# backplane.net
KiCad netlist of a schematic drawn in EAGLE
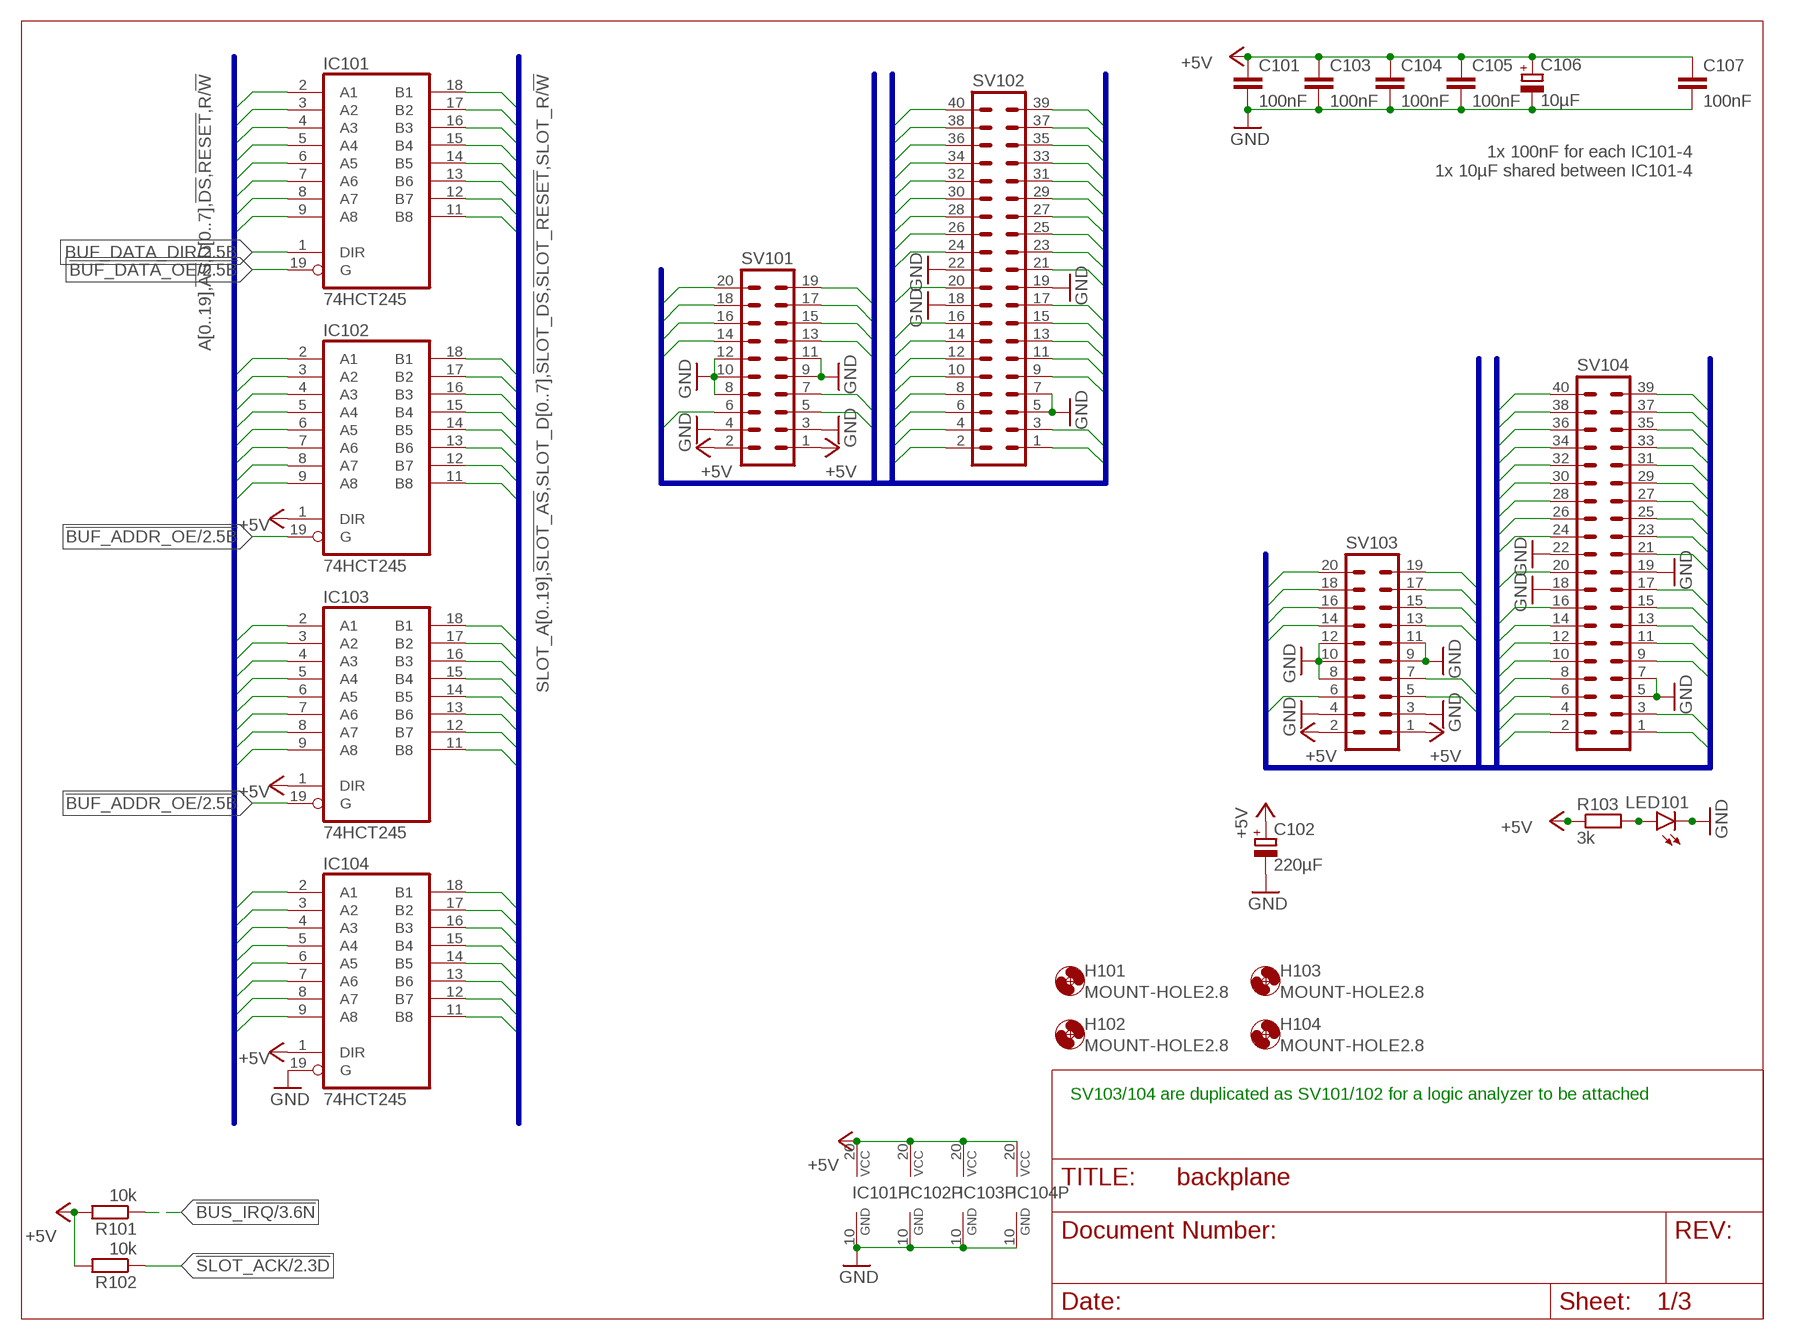
[diagram p0: schematic, sheet 1]
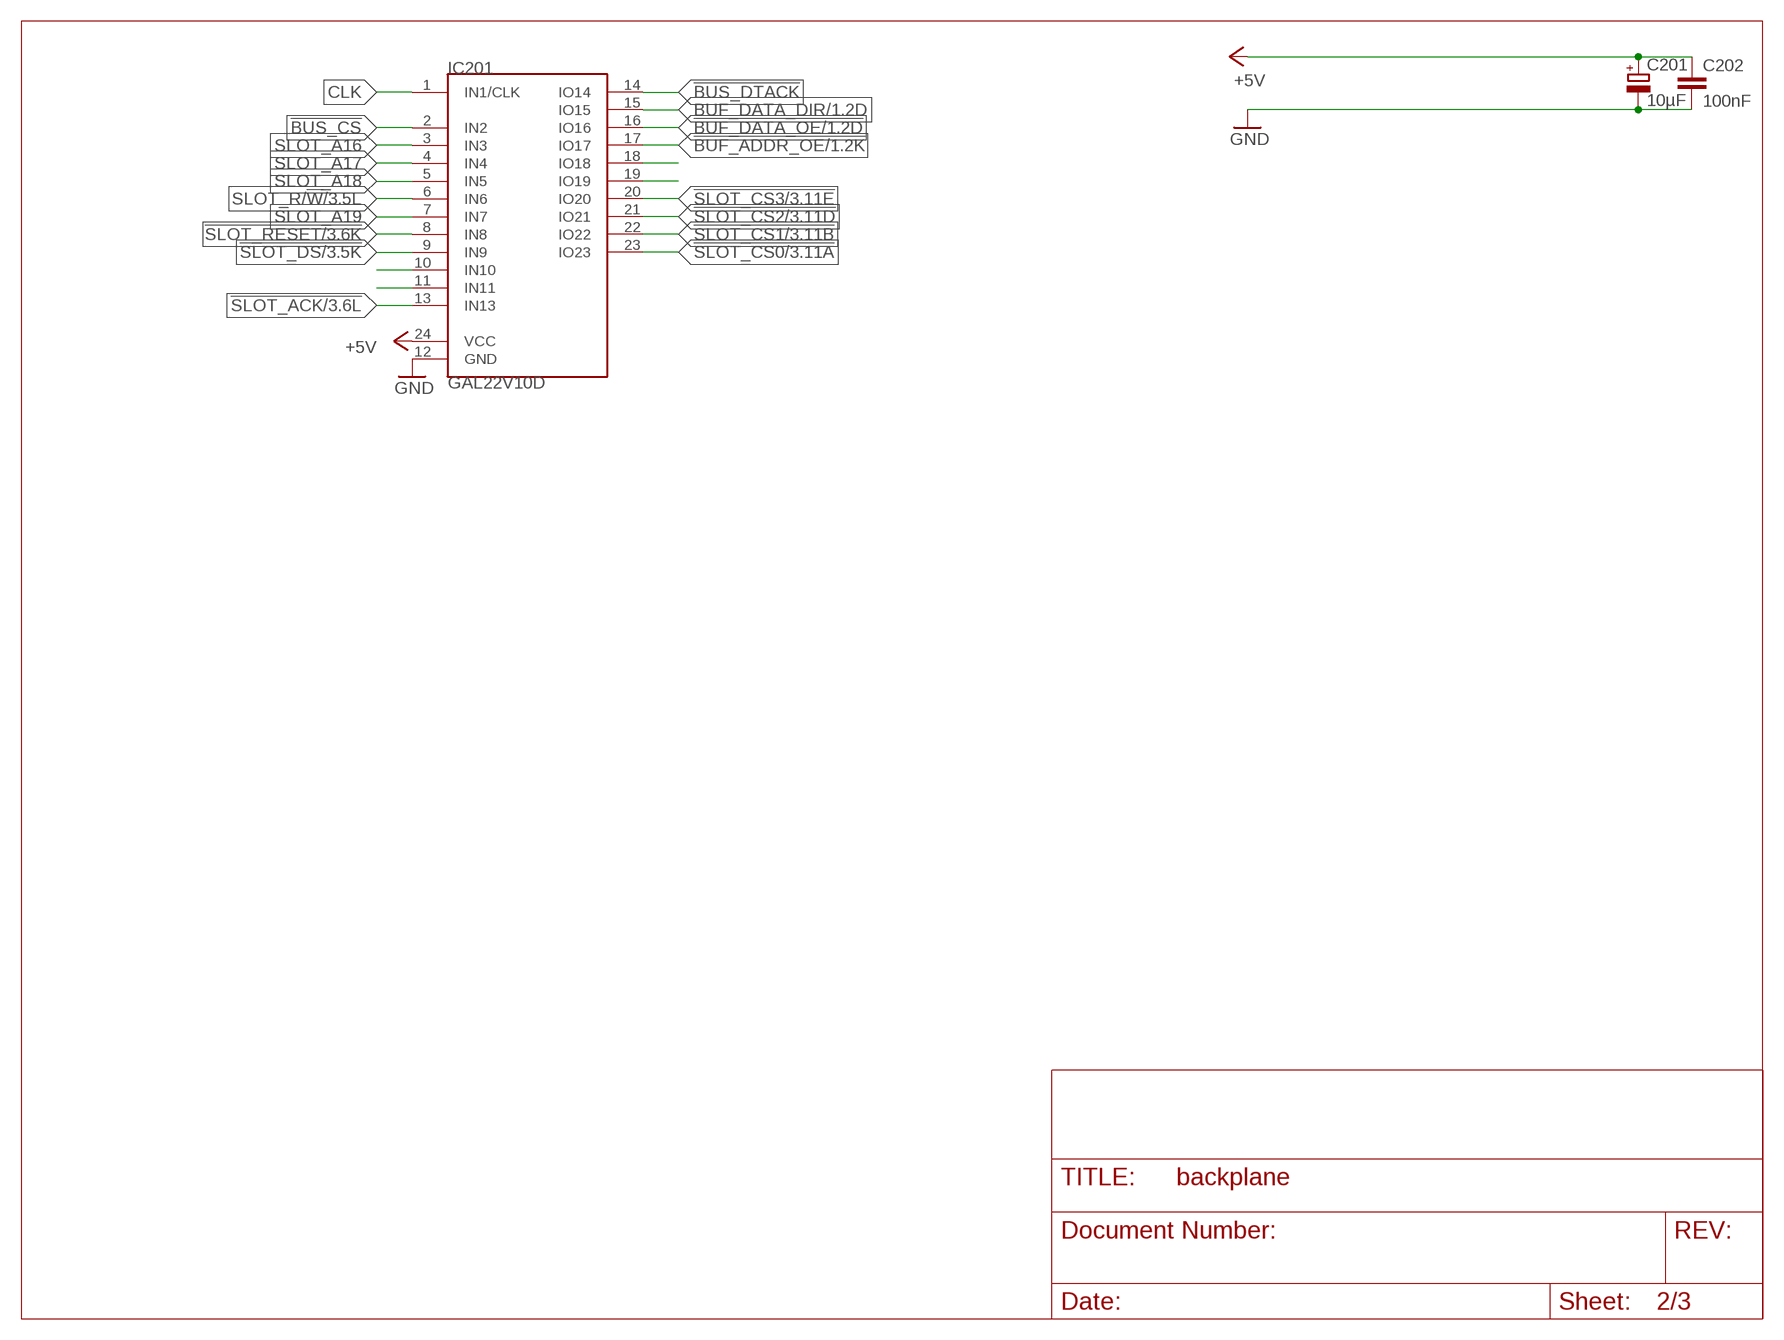
[diagram p1: schematic, sheet 2]
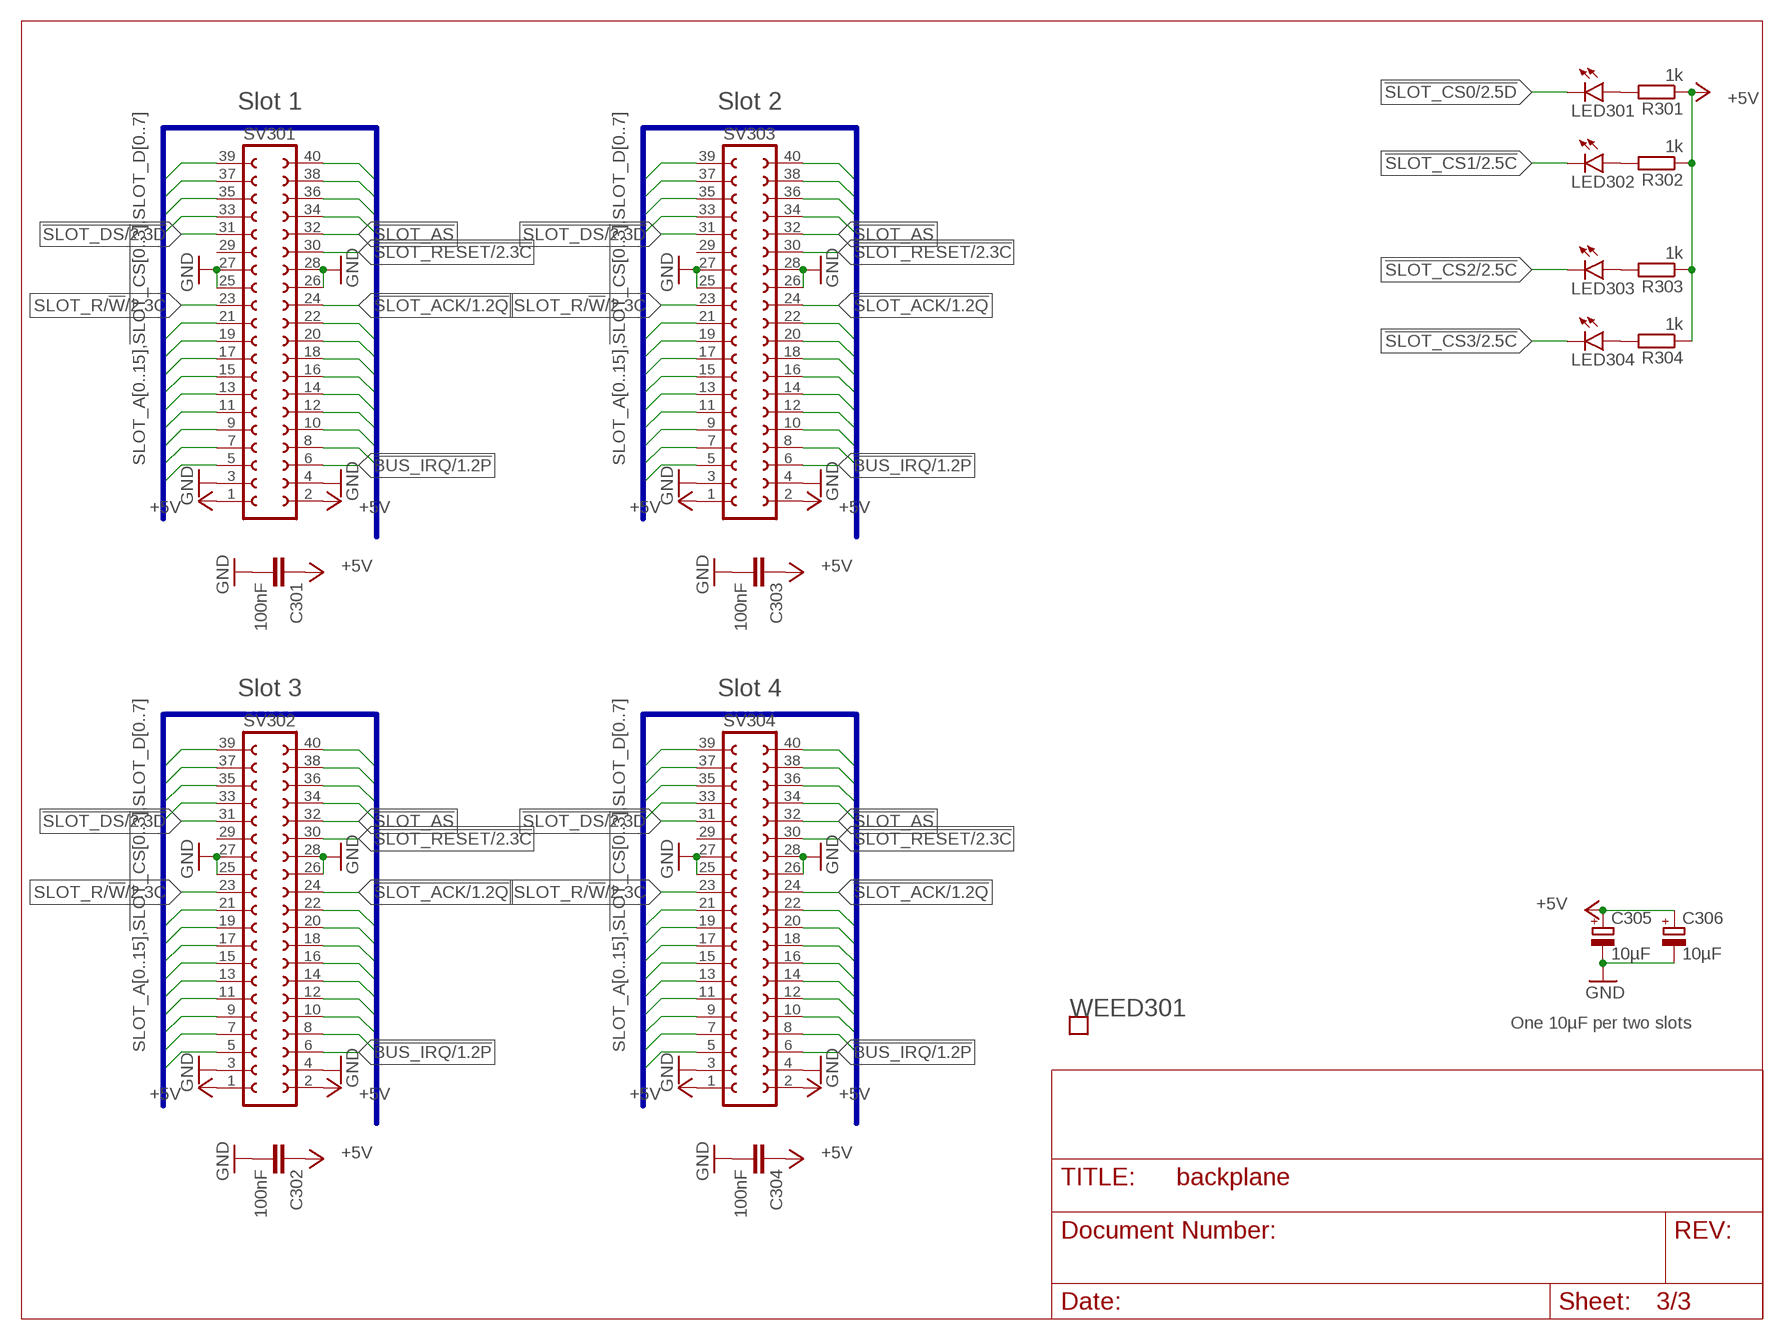
[diagram p2: schematic, sheet 3]

(export (version "E")
  (design (tool "Eeschema 10.0.6"))
  (components
    (comp (ref "C301")
      (value "100nF")
      (footprint "eagle-import:C0805")
      (libsource (lib "eagle-import") (part "C-EUC0805"))
    )
    (comp (ref "C302")
      (value "100nF")
      (footprint "eagle-import:C0805")
      (libsource (lib "eagle-import") (part "C-EUC0805"))
    )
    (comp (ref "C303")
      (value "100nF")
      (footprint "eagle-import:C0805")
      (libsource (lib "eagle-import") (part "C-EUC0805"))
    )
    (comp (ref "C304")
      (value "100nF")
      (footprint "eagle-import:C0805")
      (libsource (lib "eagle-import") (part "C-EUC0805"))
    )
    (comp (ref "C305")
      (value "10µF")
      (footprint "eagle-import:SMC_B")
      (libsource (lib "eagle-import") (part "CPOL-EUSMCB"))
    )
    (comp (ref "C306")
      (value "10µF")
      (footprint "eagle-import:SMC_B")
      (libsource (lib "eagle-import") (part "CPOL-EUSMCB"))
    )
    (comp (ref "LED301")
      (value "LEDCHIPLED_1206")
      (footprint "eagle-import:CHIPLED_1206")
      (libsource (lib "eagle-import") (part "LEDCHIPLED_1206"))
    )
    (comp (ref "LED302")
      (value "LEDCHIPLED_1206")
      (footprint "eagle-import:CHIPLED_1206")
      (libsource (lib "eagle-import") (part "LEDCHIPLED_1206"))
    )
    (comp (ref "LED303")
      (value "LEDCHIPLED_1206")
      (footprint "eagle-import:CHIPLED_1206")
      (libsource (lib "eagle-import") (part "LEDCHIPLED_1206"))
    )
    (comp (ref "LED304")
      (value "LEDCHIPLED_1206")
      (footprint "eagle-import:CHIPLED_1206")
      (libsource (lib "eagle-import") (part "LEDCHIPLED_1206"))
    )
    (comp (ref "R301")
      (value "1k")
      (footprint "eagle-import:R2012")
      (libsource (lib "eagle-import") (part "R-EU_R2012"))
    )
    (comp (ref "R302")
      (value "1k")
      (footprint "eagle-import:R2012")
      (libsource (lib "eagle-import") (part "R-EU_R2012"))
    )
    (comp (ref "R303")
      (value "1k")
      (footprint "eagle-import:R2012")
      (libsource (lib "eagle-import") (part "R-EU_R2012"))
    )
    (comp (ref "R304")
      (value "1k")
      (footprint "eagle-import:R2012")
      (libsource (lib "eagle-import") (part "R-EU_R2012"))
    )
    (comp (ref "SV301")
      (value "FE20-2")
      (footprint "eagle-import:FE20-2")
      (libsource (lib "eagle-import") (part "FE20-2"))
    )
    (comp (ref "SV302")
      (value "FE20-2")
      (footprint "eagle-import:FE20-2")
      (libsource (lib "eagle-import") (part "FE20-2"))
    )
    (comp (ref "SV303")
      (value "FE20-2")
      (footprint "eagle-import:FE20-2")
      (libsource (lib "eagle-import") (part "FE20-2"))
    )
    (comp (ref "SV304")
      (value "FE20-2")
      (footprint "eagle-import:FE20-2")
      (libsource (lib "eagle-import") (part "FE20-2"))
    )
    (comp (ref "WEED301")
      (value "WEED")
      (footprint "eagle-import:DOINK")
      (libsource (lib "eagle-import") (part "WEED"))
    )
    (comp (ref "C201")
      (value "10µF")
      (footprint "eagle-import:SMC_B")
      (libsource (lib "eagle-import") (part "CPOL-EUSMCB"))
    )
    (comp (ref "C202")
      (value "100nF")
      (footprint "eagle-import:C0805")
      (libsource (lib "eagle-import") (part "C-EUC0805"))
    )
    (comp (ref "IC201")
      (value "GAL22V10D")
      (footprint "eagle-import:DIL24S")
      (libsource (lib "eagle-import") (part "GAL22V10DIP24"))
    )
    (comp (ref "C101")
      (value "100nF")
      (footprint "eagle-import:C0805")
      (libsource (lib "eagle-import") (part "C-EUC0805"))
    )
    (comp (ref "C102")
      (value "220µF")
      (footprint "eagle-import:E3,5-8")
      (libsource (lib "eagle-import") (part "CPOL-EUE3.5-8"))
    )
    (comp (ref "C103")
      (value "100nF")
      (footprint "eagle-import:C0805")
      (libsource (lib "eagle-import") (part "C-EUC0805"))
    )
    (comp (ref "C104")
      (value "100nF")
      (footprint "eagle-import:C0805")
      (libsource (lib "eagle-import") (part "C-EUC0805"))
    )
    (comp (ref "C105")
      (value "100nF")
      (footprint "eagle-import:C0805")
      (libsource (lib "eagle-import") (part "C-EUC0805"))
    )
    (comp (ref "C106")
      (value "10µF")
      (footprint "eagle-import:SMC_B")
      (libsource (lib "eagle-import") (part "CPOL-EUSMCB"))
    )
    (comp (ref "C107")
      (value "100nF")
      (footprint "eagle-import:C0805")
      (libsource (lib "eagle-import") (part "C-EUC0805"))
    )
    (comp (ref "H101")
      (value "MOUNT-HOLE2.8")
      (footprint "eagle-import:2,8")
      (libsource (lib "eagle-import") (part "MOUNT-HOLE2.8"))
    )
    (comp (ref "H102")
      (value "MOUNT-HOLE2.8")
      (footprint "eagle-import:2,8")
      (libsource (lib "eagle-import") (part "MOUNT-HOLE2.8"))
    )
    (comp (ref "H103")
      (value "MOUNT-HOLE2.8")
      (footprint "eagle-import:2,8")
      (libsource (lib "eagle-import") (part "MOUNT-HOLE2.8"))
    )
    (comp (ref "H104")
      (value "MOUNT-HOLE2.8")
      (footprint "eagle-import:2,8")
      (libsource (lib "eagle-import") (part "MOUNT-HOLE2.8"))
    )
    (comp (ref "IC101")
      (value "74HCT245")
      (footprint "eagle-import:SO20W")
      (fields (field (name "MOUSER") "595-SN74HCT245DBR"))
      (libsource (lib "eagle-import") (part "74245DWHCT"))
    )
    (comp (ref "IC102")
      (value "74HCT245")
      (footprint "eagle-import:SO20W")
      (fields (field (name "MOUSER") "595-SN74HCT245DBR"))
      (libsource (lib "eagle-import") (part "74245DWHCT"))
    )
    (comp (ref "IC103")
      (value "74HCT245")
      (footprint "eagle-import:SO20W")
      (fields (field (name "MOUSER") "595-SN74HCT245DBR"))
      (libsource (lib "eagle-import") (part "74245DWHCT"))
    )
    (comp (ref "IC104")
      (value "74HCT245")
      (footprint "eagle-import:SO20W")
      (fields (field (name "MOUSER") "595-SN74HCT245DBR"))
      (libsource (lib "eagle-import") (part "74245DWHCT"))
    )
    (comp (ref "LED101")
      (value "LEDCHIPLED_1206")
      (footprint "eagle-import:CHIPLED_1206")
      (libsource (lib "eagle-import") (part "LEDCHIPLED_1206"))
    )
    (comp (ref "R101")
      (value "10k")
      (footprint "eagle-import:R2012")
      (libsource (lib "eagle-import") (part "R-EU_R2012"))
    )
    (comp (ref "R102")
      (value "10k")
      (footprint "eagle-import:R2012")
      (libsource (lib "eagle-import") (part "R-EU_R2012"))
    )
    (comp (ref "R103")
      (value "3k")
      (footprint "eagle-import:R2012")
      (libsource (lib "eagle-import") (part "R-EU_R2012"))
    )
    (comp (ref "SV101")
      (value "MA10-2")
      (footprint "eagle-import:MA10-2")
      (libsource (lib "eagle-import") (part "MA10-2"))
    )
    (comp (ref "SV102")
      (value "MA20-2")
      (footprint "eagle-import:MA20-2")
      (libsource (lib "eagle-import") (part "MA20-2"))
    )
    (comp (ref "SV103")
      (value "MA10-2W")
      (footprint "eagle-import:MA10-2W")
      (libsource (lib "eagle-import") (part "MA10-2W"))
    )
    (comp (ref "SV104")
      (value "MA20-2W")
      (footprint "eagle-import:MA20-2W")
      (libsource (lib "eagle-import") (part "MA20-2W"))
    )
  )
  (nets
    (net (code "1") (name "+5V") (class "Default")
      (node (ref "C101") (pin "1") (pinfunction "1_1") (pintype "passive"))
      (node (ref "C102") (pin "+") (pinfunction "+_+") (pintype "passive"))
      (node (ref "C103") (pin "1") (pinfunction "1_1") (pintype "passive"))
      (node (ref "C104") (pin "1") (pinfunction "1_1") (pintype "passive"))
      (node (ref "C105") (pin "1") (pinfunction "1_1") (pintype "passive"))
      (node (ref "C106") (pin "+") (pinfunction "+_+") (pintype "passive"))
      (node (ref "C107") (pin "1") (pinfunction "1_1") (pintype "passive"))
      (node (ref "C201") (pin "+") (pinfunction "+_+") (pintype "passive"))
      (node (ref "C202") (pin "1") (pinfunction "1_1") (pintype "passive"))
      (node (ref "C301") (pin "1") (pinfunction "1_1") (pintype "passive"))
      (node (ref "C302") (pin "1") (pinfunction "1_1") (pintype "passive"))
      (node (ref "C303") (pin "1") (pinfunction "1_1") (pintype "passive"))
      (node (ref "C304") (pin "1") (pinfunction "1_1") (pintype "passive"))
      (node (ref "C305") (pin "+") (pinfunction "+_+") (pintype "passive"))
      (node (ref "C306") (pin "+") (pinfunction "+_+") (pintype "passive"))
      (node (ref "IC101") (pin "20") (pinfunction "VCC_20") (pintype "power_in"))
      (node (ref "IC102") (pin "1") (pinfunction "DIR_1") (pintype "input"))
      (node (ref "IC102") (pin "20") (pinfunction "VCC_20") (pintype "power_in"))
      (node (ref "IC103") (pin "1") (pinfunction "DIR_1") (pintype "input"))
      (node (ref "IC103") (pin "20") (pinfunction "VCC_20") (pintype "power_in"))
      (node (ref "IC104") (pin "1") (pinfunction "DIR_1") (pintype "input"))
      (node (ref "IC104") (pin "20") (pinfunction "VCC_20") (pintype "power_in"))
      (node (ref "IC201") (pin "24") (pinfunction "VCC_24") (pintype "power_in"))
      (node (ref "R101") (pin "2") (pinfunction "2_2") (pintype "passive"))
      (node (ref "R102") (pin "2") (pinfunction "2_2") (pintype "passive"))
      (node (ref "R103") (pin "1") (pinfunction "1_1") (pintype "passive"))
      (node (ref "R301") (pin "1") (pinfunction "1_1") (pintype "passive"))
      (node (ref "R302") (pin "1") (pinfunction "1_1") (pintype "passive"))
      (node (ref "R303") (pin "1") (pinfunction "1_1") (pintype "passive"))
      (node (ref "R304") (pin "1") (pinfunction "1_1") (pintype "passive"))
      (node (ref "SV101") (pin "1") (pinfunction "1_1") (pintype "passive"))
      (node (ref "SV101") (pin "2") (pinfunction "2_2") (pintype "passive"))
      (node (ref "SV103") (pin "1") (pinfunction "1_1") (pintype "passive"))
      (node (ref "SV103") (pin "2") (pinfunction "2_2") (pintype "passive"))
      (node (ref "SV301") (pin "1") (pinfunction "1_1") (pintype "passive"))
      (node (ref "SV301") (pin "2") (pinfunction "2_2") (pintype "passive"))
      (node (ref "SV302") (pin "1") (pinfunction "1_1") (pintype "passive"))
      (node (ref "SV302") (pin "2") (pinfunction "2_2") (pintype "passive"))
      (node (ref "SV303") (pin "1") (pinfunction "1_1") (pintype "passive"))
      (node (ref "SV303") (pin "2") (pinfunction "2_2") (pintype "passive"))
      (node (ref "SV304") (pin "1") (pinfunction "1_1") (pintype "passive"))
      (node (ref "SV304") (pin "2") (pinfunction "2_2") (pintype "passive"))
    )
    (net (code "6") (name "A0") (class "Default")
      (node (ref "IC102") (pin "5") (pinfunction "A4_5") (pintype "bidirectional"))
      (node (ref "SV101") (pin "17") (pinfunction "17_17") (pintype "passive"))
      (node (ref "SV103") (pin "17") (pinfunction "17_17") (pintype "passive"))
    )
    (net (code "7") (name "A1") (class "Default")
      (node (ref "IC102") (pin "7") (pinfunction "A6_7") (pintype "bidirectional"))
      (node (ref "SV101") (pin "15") (pinfunction "15_15") (pintype "passive"))
      (node (ref "SV103") (pin "15") (pinfunction "15_15") (pintype "passive"))
    )
    (net (code "8") (name "A2") (class "Default")
      (node (ref "IC102") (pin "9") (pinfunction "A8_9") (pintype "bidirectional"))
      (node (ref "SV101") (pin "13") (pinfunction "13_13") (pintype "passive"))
      (node (ref "SV103") (pin "13") (pinfunction "13_13") (pintype "passive"))
    )
    (net (code "9") (name "A3") (class "Default")
      (node (ref "IC102") (pin "8") (pinfunction "A7_8") (pintype "bidirectional"))
      (node (ref "SV101") (pin "14") (pinfunction "14_14") (pintype "passive"))
      (node (ref "SV103") (pin "14") (pinfunction "14_14") (pintype "passive"))
    )
    (net (code "10") (name "A4") (class "Default")
      (node (ref "IC102") (pin "6") (pinfunction "A5_6") (pintype "bidirectional"))
      (node (ref "SV101") (pin "16") (pinfunction "16_16") (pintype "passive"))
      (node (ref "SV103") (pin "16") (pinfunction "16_16") (pintype "passive"))
    )
    (net (code "11") (name "A5") (class "Default")
      (node (ref "IC102") (pin "4") (pinfunction "A3_4") (pintype "bidirectional"))
      (node (ref "SV101") (pin "18") (pinfunction "18_18") (pintype "passive"))
      (node (ref "SV103") (pin "18") (pinfunction "18_18") (pintype "passive"))
    )
    (net (code "12") (name "A6") (class "Default")
      (node (ref "IC102") (pin "3") (pinfunction "A2_3") (pintype "bidirectional"))
      (node (ref "SV101") (pin "20") (pinfunction "20_20") (pintype "passive"))
      (node (ref "SV103") (pin "20") (pinfunction "20_20") (pintype "passive"))
    )
    (net (code "13") (name "A7") (class "Default")
      (node (ref "IC102") (pin "2") (pinfunction "A1_2") (pintype "bidirectional"))
      (node (ref "SV102") (pin "2") (pinfunction "2_2") (pintype "passive"))
      (node (ref "SV104") (pin "2") (pinfunction "2_2") (pintype "passive"))
    )
    (net (code "14") (name "A8") (class "Default")
      (node (ref "IC103") (pin "9") (pinfunction "A8_9") (pintype "bidirectional"))
      (node (ref "SV102") (pin "4") (pinfunction "4_4") (pintype "passive"))
      (node (ref "SV104") (pin "4") (pinfunction "4_4") (pintype "passive"))
    )
    (net (code "15") (name "A9") (class "Default")
      (node (ref "IC103") (pin "8") (pinfunction "A7_8") (pintype "bidirectional"))
      (node (ref "SV102") (pin "6") (pinfunction "6_6") (pintype "passive"))
      (node (ref "SV104") (pin "6") (pinfunction "6_6") (pintype "passive"))
    )
    (net (code "16") (name "A10") (class "Default")
      (node (ref "IC103") (pin "7") (pinfunction "A6_7") (pintype "bidirectional"))
      (node (ref "SV102") (pin "8") (pinfunction "8_8") (pintype "passive"))
      (node (ref "SV104") (pin "8") (pinfunction "8_8") (pintype "passive"))
    )
    (net (code "17") (name "A11") (class "Default")
      (node (ref "IC103") (pin "6") (pinfunction "A5_6") (pintype "bidirectional"))
      (node (ref "SV102") (pin "10") (pinfunction "10_10") (pintype "passive"))
      (node (ref "SV104") (pin "10") (pinfunction "10_10") (pintype "passive"))
    )
    (net (code "18") (name "A12") (class "Default")
      (node (ref "IC103") (pin "5") (pinfunction "A4_5") (pintype "bidirectional"))
      (node (ref "SV102") (pin "12") (pinfunction "12_12") (pintype "passive"))
      (node (ref "SV104") (pin "12") (pinfunction "12_12") (pintype "passive"))
    )
    (net (code "19") (name "A13") (class "Default")
      (node (ref "IC103") (pin "4") (pinfunction "A3_4") (pintype "bidirectional"))
      (node (ref "SV102") (pin "14") (pinfunction "14_14") (pintype "passive"))
      (node (ref "SV104") (pin "14") (pinfunction "14_14") (pintype "passive"))
    )
    (net (code "20") (name "A14") (class "Default")
      (node (ref "IC103") (pin "3") (pinfunction "A2_3") (pintype "bidirectional"))
      (node (ref "SV102") (pin "16") (pinfunction "16_16") (pintype "passive"))
      (node (ref "SV104") (pin "16") (pinfunction "16_16") (pintype "passive"))
    )
    (net (code "21") (name "A15") (class "Default")
      (node (ref "IC103") (pin "2") (pinfunction "A1_2") (pintype "bidirectional"))
      (node (ref "SV102") (pin "20") (pinfunction "20_20") (pintype "passive"))
      (node (ref "SV104") (pin "20") (pinfunction "20_20") (pintype "passive"))
    )
    (net (code "22") (name "A16") (class "Default")
      (node (ref "IC104") (pin "8") (pinfunction "A7_8") (pintype "bidirectional"))
      (node (ref "SV102") (pin "24") (pinfunction "24_24") (pintype "passive"))
      (node (ref "SV104") (pin "24") (pinfunction "24_24") (pintype "passive"))
    )
    (net (code "23") (name "A17") (class "Default")
      (node (ref "IC104") (pin "7") (pinfunction "A6_7") (pintype "bidirectional"))
      (node (ref "SV102") (pin "26") (pinfunction "26_26") (pintype "passive"))
      (node (ref "SV104") (pin "26") (pinfunction "26_26") (pintype "passive"))
    )
    (net (code "24") (name "A18") (class "Default")
      (node (ref "IC104") (pin "6") (pinfunction "A5_6") (pintype "bidirectional"))
      (node (ref "SV102") (pin "28") (pinfunction "28_28") (pintype "passive"))
      (node (ref "SV104") (pin "28") (pinfunction "28_28") (pintype "passive"))
    )
    (net (code "25") (name "A19") (class "Default")
      (node (ref "IC104") (pin "4") (pinfunction "A3_4") (pintype "bidirectional"))
      (node (ref "SV102") (pin "30") (pinfunction "30_30") (pintype "passive"))
      (node (ref "SV104") (pin "30") (pinfunction "30_30") (pintype "passive"))
    )
    (net (code "26") (name "BUF_DATA_DIR") (class "Default")
      (node (ref "IC101") (pin "1") (pinfunction "DIR_1") (pintype "input"))
      (node (ref "IC201") (pin "15") (pinfunction "IO15_15") (pintype "bidirectional"))
    )
    (net (code "27") (name "CLK") (class "Default")
      (node (ref "IC201") (pin "1") (pinfunction "IN1/CLK_1") (pintype "input"))
      (node (ref "SV102") (pin "21") (pinfunction "21_21") (pintype "passive"))
      (node (ref "SV104") (pin "21") (pinfunction "21_21") (pintype "passive"))
    )
    (net (code "28") (name "D0") (class "Default")
      (node (ref "IC101") (pin "7") (pinfunction "A6_7") (pintype "bidirectional"))
      (node (ref "SV102") (pin "35") (pinfunction "35_35") (pintype "passive"))
      (node (ref "SV104") (pin "35") (pinfunction "35_35") (pintype "passive"))
    )
    (net (code "29") (name "D1") (class "Default")
      (node (ref "IC101") (pin "5") (pinfunction "A4_5") (pintype "bidirectional"))
      (node (ref "SV102") (pin "37") (pinfunction "37_37") (pintype "passive"))
      (node (ref "SV104") (pin "37") (pinfunction "37_37") (pintype "passive"))
    )
    (net (code "30") (name "D2") (class "Default")
      (node (ref "IC101") (pin "3") (pinfunction "A2_3") (pintype "bidirectional"))
      (node (ref "SV102") (pin "39") (pinfunction "39_39") (pintype "passive"))
      (node (ref "SV104") (pin "39") (pinfunction "39_39") (pintype "passive"))
    )
    (net (code "31") (name "D3") (class "Default")
      (node (ref "IC101") (pin "2") (pinfunction "A1_2") (pintype "bidirectional"))
      (node (ref "SV102") (pin "40") (pinfunction "40_40") (pintype "passive"))
      (node (ref "SV104") (pin "40") (pinfunction "40_40") (pintype "passive"))
    )
    (net (code "32") (name "D4") (class "Default")
      (node (ref "IC101") (pin "4") (pinfunction "A3_4") (pintype "bidirectional"))
      (node (ref "SV102") (pin "38") (pinfunction "38_38") (pintype "passive"))
      (node (ref "SV104") (pin "38") (pinfunction "38_38") (pintype "passive"))
    )
    (net (code "33") (name "D5") (class "Default")
      (node (ref "IC101") (pin "6") (pinfunction "A5_6") (pintype "bidirectional"))
      (node (ref "SV102") (pin "36") (pinfunction "36_36") (pintype "passive"))
      (node (ref "SV104") (pin "36") (pinfunction "36_36") (pintype "passive"))
    )
    (net (code "34") (name "D6") (class "Default")
      (node (ref "IC101") (pin "8") (pinfunction "A7_8") (pintype "bidirectional"))
      (node (ref "SV102") (pin "34") (pinfunction "34_34") (pintype "passive"))
      (node (ref "SV104") (pin "34") (pinfunction "34_34") (pintype "passive"))
    )
    (net (code "35") (name "D7") (class "Default")
      (node (ref "IC101") (pin "9") (pinfunction "A8_9") (pintype "bidirectional"))
      (node (ref "SV102") (pin "32") (pinfunction "32_32") (pintype "passive"))
      (node (ref "SV104") (pin "32") (pinfunction "32_32") (pintype "passive"))
    )
    (net (code "36") (name "E") (class "Default")
      (node (ref "SV102") (pin "13") (pinfunction "13_13") (pintype "passive"))
      (node (ref "SV104") (pin "13") (pinfunction "13_13") (pintype "passive"))
    )
    (net (code "37") (name "FC0") (class "Default")
      (node (ref "SV101") (pin "19") (pinfunction "19_19") (pintype "passive"))
      (node (ref "SV103") (pin "19") (pinfunction "19_19") (pintype "passive"))
    )
    (net (code "38") (name "FC1") (class "Default")
      (node (ref "SV102") (pin "1") (pinfunction "1_1") (pintype "passive"))
      (node (ref "SV104") (pin "1") (pinfunction "1_1") (pintype "passive"))
    )
    (net (code "39") (name "FC2") (class "Default")
      (node (ref "SV102") (pin "3") (pinfunction "3_3") (pintype "passive"))
      (node (ref "SV104") (pin "3") (pinfunction "3_3") (pintype "passive"))
    )
    (net (code "40") (name "GND") (class "Default")
      (node (ref "C101") (pin "2") (pinfunction "2_2") (pintype "passive"))
      (node (ref "C102") (pin "-") (pinfunction "-_-") (pintype "passive"))
      (node (ref "C103") (pin "2") (pinfunction "2_2") (pintype "passive"))
      (node (ref "C104") (pin "2") (pinfunction "2_2") (pintype "passive"))
      (node (ref "C105") (pin "2") (pinfunction "2_2") (pintype "passive"))
      (node (ref "C106") (pin "-") (pinfunction "-_-") (pintype "passive"))
      (node (ref "C107") (pin "2") (pinfunction "2_2") (pintype "passive"))
      (node (ref "C201") (pin "-") (pinfunction "-_-") (pintype "passive"))
      (node (ref "C202") (pin "2") (pinfunction "2_2") (pintype "passive"))
      (node (ref "C301") (pin "2") (pinfunction "2_2") (pintype "passive"))
      (node (ref "C302") (pin "2") (pinfunction "2_2") (pintype "passive"))
      (node (ref "C303") (pin "2") (pinfunction "2_2") (pintype "passive"))
      (node (ref "C304") (pin "2") (pinfunction "2_2") (pintype "passive"))
      (node (ref "C305") (pin "-") (pinfunction "-_-") (pintype "passive"))
      (node (ref "C306") (pin "-") (pinfunction "-_-") (pintype "passive"))
      (node (ref "IC101") (pin "10") (pinfunction "GND_10") (pintype "power_in"))
      (node (ref "IC102") (pin "10") (pinfunction "GND_10") (pintype "power_in"))
      (node (ref "IC103") (pin "10") (pinfunction "GND_10") (pintype "power_in"))
      (node (ref "IC104") (pin "10") (pinfunction "GND_10") (pintype "power_in"))
      (node (ref "IC104") (pin "19") (pinfunction "G_19") (pintype "input"))
      (node (ref "IC201") (pin "12") (pinfunction "GND_12") (pintype "power_in"))
      (node (ref "LED101") (pin "C") (pinfunction "C_C") (pintype "passive"))
      (node (ref "SV101") (pin "10") (pinfunction "10_10") (pintype "passive"))
      (node (ref "SV101") (pin "11") (pinfunction "11_11") (pintype "passive"))
      (node (ref "SV101") (pin "12") (pinfunction "12_12") (pintype "passive"))
      (node (ref "SV101") (pin "3") (pinfunction "3_3") (pintype "passive"))
      (node (ref "SV101") (pin "4") (pinfunction "4_4") (pintype "passive"))
      (node (ref "SV101") (pin "8") (pinfunction "8_8") (pintype "passive"))
      (node (ref "SV101") (pin "9") (pinfunction "9_9") (pintype "passive"))
      (node (ref "SV102") (pin "18") (pinfunction "18_18") (pintype "passive"))
      (node (ref "SV102") (pin "19") (pinfunction "19_19") (pintype "passive"))
      (node (ref "SV102") (pin "22") (pinfunction "22_22") (pintype "passive"))
      (node (ref "SV102") (pin "5") (pinfunction "5_5") (pintype "passive"))
      (node (ref "SV102") (pin "7") (pinfunction "7_7") (pintype "passive"))
      (node (ref "SV103") (pin "10") (pinfunction "10_10") (pintype "passive"))
      (node (ref "SV103") (pin "11") (pinfunction "11_11") (pintype "passive"))
      (node (ref "SV103") (pin "12") (pinfunction "12_12") (pintype "passive"))
      (node (ref "SV103") (pin "3") (pinfunction "3_3") (pintype "passive"))
      (node (ref "SV103") (pin "4") (pinfunction "4_4") (pintype "passive"))
      (node (ref "SV103") (pin "8") (pinfunction "8_8") (pintype "passive"))
      (node (ref "SV103") (pin "9") (pinfunction "9_9") (pintype "passive"))
      (node (ref "SV104") (pin "18") (pinfunction "18_18") (pintype "passive"))
      (node (ref "SV104") (pin "19") (pinfunction "19_19") (pintype "passive"))
      (node (ref "SV104") (pin "22") (pinfunction "22_22") (pintype "passive"))
      (node (ref "SV104") (pin "5") (pinfunction "5_5") (pintype "passive"))
      (node (ref "SV104") (pin "7") (pinfunction "7_7") (pintype "passive"))
      (node (ref "SV301") (pin "25") (pinfunction "25_25") (pintype "passive"))
      (node (ref "SV301") (pin "26") (pinfunction "26_26") (pintype "passive"))
      (node (ref "SV301") (pin "27") (pinfunction "27_27") (pintype "passive"))
      (node (ref "SV301") (pin "28") (pinfunction "28_28") (pintype "passive"))
      (node (ref "SV301") (pin "3") (pinfunction "3_3") (pintype "passive"))
      (node (ref "SV301") (pin "4") (pinfunction "4_4") (pintype "passive"))
      (node (ref "SV302") (pin "25") (pinfunction "25_25") (pintype "passive"))
      (node (ref "SV302") (pin "26") (pinfunction "26_26") (pintype "passive"))
      (node (ref "SV302") (pin "27") (pinfunction "27_27") (pintype "passive"))
      (node (ref "SV302") (pin "28") (pinfunction "28_28") (pintype "passive"))
      (node (ref "SV302") (pin "3") (pinfunction "3_3") (pintype "passive"))
      (node (ref "SV302") (pin "4") (pinfunction "4_4") (pintype "passive"))
      (node (ref "SV303") (pin "25") (pinfunction "25_25") (pintype "passive"))
      (node (ref "SV303") (pin "26") (pinfunction "26_26") (pintype "passive"))
      (node (ref "SV303") (pin "27") (pinfunction "27_27") (pintype "passive"))
      (node (ref "SV303") (pin "28") (pinfunction "28_28") (pintype "passive"))
      (node (ref "SV303") (pin "3") (pinfunction "3_3") (pintype "passive"))
      (node (ref "SV303") (pin "4") (pinfunction "4_4") (pintype "passive"))
      (node (ref "SV304") (pin "25") (pinfunction "25_25") (pintype "passive"))
      (node (ref "SV304") (pin "26") (pinfunction "26_26") (pintype "passive"))
      (node (ref "SV304") (pin "27") (pinfunction "27_27") (pintype "passive"))
      (node (ref "SV304") (pin "28") (pinfunction "28_28") (pintype "passive"))
      (node (ref "SV304") (pin "3") (pinfunction "3_3") (pintype "passive"))
      (node (ref "SV304") (pin "4") (pinfunction "4_4") (pintype "passive"))
    )
    (net (code "41") (name "Net-(LED101-PadA)") (class "Default")
      (node (ref "LED101") (pin "A") (pinfunction "A_A") (pintype "passive"))
      (node (ref "R103") (pin "2") (pinfunction "2_2") (pintype "passive"))
    )
    (net (code "42") (name "Net-(LED301-PadA)") (class "Default")
      (node (ref "LED301") (pin "A") (pinfunction "A_A") (pintype "passive"))
      (node (ref "R301") (pin "2") (pinfunction "2_2") (pintype "passive"))
    )
    (net (code "43") (name "Net-(LED302-PadA)") (class "Default")
      (node (ref "LED302") (pin "A") (pinfunction "A_A") (pintype "passive"))
      (node (ref "R302") (pin "2") (pinfunction "2_2") (pintype "passive"))
    )
    (net (code "44") (name "Net-(LED303-PadA)") (class "Default")
      (node (ref "LED303") (pin "A") (pinfunction "A_A") (pintype "passive"))
      (node (ref "R303") (pin "2") (pinfunction "2_2") (pintype "passive"))
    )
    (net (code "45") (name "Net-(LED304-PadA)") (class "Default")
      (node (ref "LED304") (pin "A") (pinfunction "A_A") (pintype "passive"))
      (node (ref "R304") (pin "2") (pinfunction "2_2") (pintype "passive"))
    )
    (net (code "46") (name "R{slash}~{W}") (class "Default")
      (node (ref "IC104") (pin "5") (pinfunction "A4_5") (pintype "bidirectional"))
      (node (ref "SV102") (pin "29") (pinfunction "29_29") (pintype "passive"))
      (node (ref "SV104") (pin "29") (pinfunction "29_29") (pintype "passive"))
    )
    (net (code "47") (name "SLOT_A0") (class "Default")
      (node (ref "IC102") (pin "15") (pinfunction "B4_15") (pintype "bidirectional"))
      (node (ref "SV301") (pin "12") (pinfunction "12_12") (pintype "passive"))
      (node (ref "SV302") (pin "12") (pinfunction "12_12") (pintype "passive"))
      (node (ref "SV303") (pin "12") (pinfunction "12_12") (pintype "passive"))
      (node (ref "SV304") (pin "12") (pinfunction "12_12") (pintype "passive"))
    )
    (net (code "48") (name "SLOT_A1") (class "Default")
      (node (ref "IC102") (pin "13") (pinfunction "B6_13") (pintype "bidirectional"))
      (node (ref "SV301") (pin "10") (pinfunction "10_10") (pintype "passive"))
      (node (ref "SV302") (pin "10") (pinfunction "10_10") (pintype "passive"))
      (node (ref "SV303") (pin "10") (pinfunction "10_10") (pintype "passive"))
      (node (ref "SV304") (pin "10") (pinfunction "10_10") (pintype "passive"))
    )
    (net (code "49") (name "SLOT_A2") (class "Default")
      (node (ref "IC102") (pin "11") (pinfunction "B8_11") (pintype "bidirectional"))
      (node (ref "SV301") (pin "8") (pinfunction "8_8") (pintype "passive"))
      (node (ref "SV302") (pin "8") (pinfunction "8_8") (pintype "passive"))
      (node (ref "SV303") (pin "8") (pinfunction "8_8") (pintype "passive"))
      (node (ref "SV304") (pin "8") (pinfunction "8_8") (pintype "passive"))
    )
    (net (code "50") (name "SLOT_A3") (class "Default")
      (node (ref "IC102") (pin "12") (pinfunction "B7_12") (pintype "bidirectional"))
      (node (ref "SV301") (pin "7") (pinfunction "7_7") (pintype "passive"))
      (node (ref "SV302") (pin "7") (pinfunction "7_7") (pintype "passive"))
      (node (ref "SV303") (pin "7") (pinfunction "7_7") (pintype "passive"))
      (node (ref "SV304") (pin "7") (pinfunction "7_7") (pintype "passive"))
    )
    (net (code "51") (name "SLOT_A4") (class "Default")
      (node (ref "IC102") (pin "14") (pinfunction "B5_14") (pintype "bidirectional"))
      (node (ref "SV301") (pin "9") (pinfunction "9_9") (pintype "passive"))
      (node (ref "SV302") (pin "9") (pinfunction "9_9") (pintype "passive"))
      (node (ref "SV303") (pin "9") (pinfunction "9_9") (pintype "passive"))
      (node (ref "SV304") (pin "9") (pinfunction "9_9") (pintype "passive"))
    )
    (net (code "52") (name "SLOT_A5") (class "Default")
      (node (ref "IC102") (pin "16") (pinfunction "B3_16") (pintype "bidirectional"))
      (node (ref "SV301") (pin "11") (pinfunction "11_11") (pintype "passive"))
      (node (ref "SV302") (pin "11") (pinfunction "11_11") (pintype "passive"))
      (node (ref "SV303") (pin "11") (pinfunction "11_11") (pintype "passive"))
      (node (ref "SV304") (pin "11") (pinfunction "11_11") (pintype "passive"))
    )
    (net (code "53") (name "SLOT_A6") (class "Default")
      (node (ref "IC102") (pin "17") (pinfunction "B2_17") (pintype "bidirectional"))
      (node (ref "SV301") (pin "14") (pinfunction "14_14") (pintype "passive"))
      (node (ref "SV302") (pin "14") (pinfunction "14_14") (pintype "passive"))
      (node (ref "SV303") (pin "14") (pinfunction "14_14") (pintype "passive"))
      (node (ref "SV304") (pin "14") (pinfunction "14_14") (pintype "passive"))
    )
    (net (code "54") (name "SLOT_A7") (class "Default")
      (node (ref "IC102") (pin "18") (pinfunction "B1_18") (pintype "bidirectional"))
      (node (ref "SV301") (pin "13") (pinfunction "13_13") (pintype "passive"))
      (node (ref "SV302") (pin "13") (pinfunction "13_13") (pintype "passive"))
      (node (ref "SV303") (pin "13") (pinfunction "13_13") (pintype "passive"))
      (node (ref "SV304") (pin "13") (pinfunction "13_13") (pintype "passive"))
    )
    (net (code "55") (name "SLOT_A8") (class "Default")
      (node (ref "IC103") (pin "11") (pinfunction "B8_11") (pintype "bidirectional"))
      (node (ref "SV301") (pin "16") (pinfunction "16_16") (pintype "passive"))
      (node (ref "SV302") (pin "16") (pinfunction "16_16") (pintype "passive"))
      (node (ref "SV303") (pin "16") (pinfunction "16_16") (pintype "passive"))
      (node (ref "SV304") (pin "16") (pinfunction "16_16") (pintype "passive"))
    )
    (net (code "56") (name "SLOT_A9") (class "Default")
      (node (ref "IC103") (pin "12") (pinfunction "B7_12") (pintype "bidirectional"))
      (node (ref "SV301") (pin "15") (pinfunction "15_15") (pintype "passive"))
      (node (ref "SV302") (pin "15") (pinfunction "15_15") (pintype "passive"))
      (node (ref "SV303") (pin "15") (pinfunction "15_15") (pintype "passive"))
      (node (ref "SV304") (pin "15") (pinfunction "15_15") (pintype "passive"))
    )
    (net (code "57") (name "SLOT_A10") (class "Default")
      (node (ref "IC103") (pin "13") (pinfunction "B6_13") (pintype "bidirectional"))
      (node (ref "SV301") (pin "18") (pinfunction "18_18") (pintype "passive"))
      (node (ref "SV302") (pin "18") (pinfunction "18_18") (pintype "passive"))
      (node (ref "SV303") (pin "18") (pinfunction "18_18") (pintype "passive"))
      (node (ref "SV304") (pin "18") (pinfunction "18_18") (pintype "passive"))
    )
    (net (code "58") (name "SLOT_A11") (class "Default")
      (node (ref "IC103") (pin "14") (pinfunction "B5_14") (pintype "bidirectional"))
      (node (ref "SV301") (pin "17") (pinfunction "17_17") (pintype "passive"))
      (node (ref "SV302") (pin "17") (pinfunction "17_17") (pintype "passive"))
      (node (ref "SV303") (pin "17") (pinfunction "17_17") (pintype "passive"))
      (node (ref "SV304") (pin "17") (pinfunction "17_17") (pintype "passive"))
    )
    (net (code "59") (name "SLOT_A12") (class "Default")
      (node (ref "IC103") (pin "15") (pinfunction "B4_15") (pintype "bidirectional"))
      (node (ref "SV301") (pin "20") (pinfunction "20_20") (pintype "passive"))
      (node (ref "SV302") (pin "20") (pinfunction "20_20") (pintype "passive"))
      (node (ref "SV303") (pin "20") (pinfunction "20_20") (pintype "passive"))
      (node (ref "SV304") (pin "20") (pinfunction "20_20") (pintype "passive"))
    )
    (net (code "60") (name "SLOT_A13") (class "Default")
      (node (ref "IC103") (pin "16") (pinfunction "B3_16") (pintype "bidirectional"))
      (node (ref "SV301") (pin "19") (pinfunction "19_19") (pintype "passive"))
      (node (ref "SV302") (pin "19") (pinfunction "19_19") (pintype "passive"))
      (node (ref "SV303") (pin "19") (pinfunction "19_19") (pintype "passive"))
      (node (ref "SV304") (pin "19") (pinfunction "19_19") (pintype "passive"))
    )
    (net (code "61") (name "SLOT_A14") (class "Default")
      (node (ref "IC103") (pin "17") (pinfunction "B2_17") (pintype "bidirectional"))
      (node (ref "SV301") (pin "22") (pinfunction "22_22") (pintype "passive"))
      (node (ref "SV302") (pin "22") (pinfunction "22_22") (pintype "passive"))
      (node (ref "SV303") (pin "22") (pinfunction "22_22") (pintype "passive"))
      (node (ref "SV304") (pin "22") (pinfunction "22_22") (pintype "passive"))
    )
    (net (code "62") (name "SLOT_A15") (class "Default")
      (node (ref "IC103") (pin "18") (pinfunction "B1_18") (pintype "bidirectional"))
      (node (ref "SV301") (pin "21") (pinfunction "21_21") (pintype "passive"))
      (node (ref "SV302") (pin "21") (pinfunction "21_21") (pintype "passive"))
      (node (ref "SV303") (pin "21") (pinfunction "21_21") (pintype "passive"))
      (node (ref "SV304") (pin "21") (pinfunction "21_21") (pintype "passive"))
    )
    (net (code "63") (name "SLOT_A16") (class "Default")
      (node (ref "IC104") (pin "12") (pinfunction "B7_12") (pintype "bidirectional"))
      (node (ref "IC201") (pin "3") (pinfunction "IN3_3") (pintype "input"))
    )
    (net (code "64") (name "SLOT_A17") (class "Default")
      (node (ref "IC104") (pin "13") (pinfunction "B6_13") (pintype "bidirectional"))
      (node (ref "IC201") (pin "4") (pinfunction "IN4_4") (pintype "input"))
    )
    (net (code "65") (name "SLOT_A18") (class "Default")
      (node (ref "IC104") (pin "14") (pinfunction "B5_14") (pintype "bidirectional"))
      (node (ref "IC201") (pin "5") (pinfunction "IN5_5") (pintype "input"))
    )
    (net (code "66") (name "SLOT_A19") (class "Default")
      (node (ref "IC104") (pin "16") (pinfunction "B3_16") (pintype "bidirectional"))
      (node (ref "IC201") (pin "7") (pinfunction "IN7_7") (pintype "input"))
    )
    (net (code "67") (name "SLOT_D0") (class "Default")
      (node (ref "IC101") (pin "13") (pinfunction "B6_13") (pintype "bidirectional"))
      (node (ref "SV301") (pin "35") (pinfunction "35_35") (pintype "passive"))
      (node (ref "SV302") (pin "35") (pinfunction "35_35") (pintype "passive"))
      (node (ref "SV303") (pin "35") (pinfunction "35_35") (pintype "passive"))
      (node (ref "SV304") (pin "35") (pinfunction "35_35") (pintype "passive"))
    )
    (net (code "68") (name "SLOT_D1") (class "Default")
      (node (ref "IC101") (pin "15") (pinfunction "B4_15") (pintype "bidirectional"))
      (node (ref "SV301") (pin "37") (pinfunction "37_37") (pintype "passive"))
      (node (ref "SV302") (pin "37") (pinfunction "37_37") (pintype "passive"))
      (node (ref "SV303") (pin "37") (pinfunction "37_37") (pintype "passive"))
      (node (ref "SV304") (pin "37") (pinfunction "37_37") (pintype "passive"))
    )
    (net (code "69") (name "SLOT_D2") (class "Default")
      (node (ref "IC101") (pin "17") (pinfunction "B2_17") (pintype "bidirectional"))
      (node (ref "SV301") (pin "39") (pinfunction "39_39") (pintype "passive"))
      (node (ref "SV302") (pin "39") (pinfunction "39_39") (pintype "passive"))
      (node (ref "SV303") (pin "39") (pinfunction "39_39") (pintype "passive"))
      (node (ref "SV304") (pin "39") (pinfunction "39_39") (pintype "passive"))
    )
    (net (code "70") (name "SLOT_D3") (class "Default")
      (node (ref "IC101") (pin "18") (pinfunction "B1_18") (pintype "bidirectional"))
      (node (ref "SV301") (pin "40") (pinfunction "40_40") (pintype "passive"))
      (node (ref "SV302") (pin "40") (pinfunction "40_40") (pintype "passive"))
      (node (ref "SV303") (pin "40") (pinfunction "40_40") (pintype "passive"))
      (node (ref "SV304") (pin "40") (pinfunction "40_40") (pintype "passive"))
    )
    (net (code "71") (name "SLOT_D4") (class "Default")
      (node (ref "IC101") (pin "16") (pinfunction "B3_16") (pintype "bidirectional"))
      (node (ref "SV301") (pin "38") (pinfunction "38_38") (pintype "passive"))
      (node (ref "SV302") (pin "38") (pinfunction "38_38") (pintype "passive"))
      (node (ref "SV303") (pin "38") (pinfunction "38_38") (pintype "passive"))
      (node (ref "SV304") (pin "38") (pinfunction "38_38") (pintype "passive"))
    )
    (net (code "72") (name "SLOT_D5") (class "Default")
      (node (ref "IC101") (pin "14") (pinfunction "B5_14") (pintype "bidirectional"))
      (node (ref "SV301") (pin "36") (pinfunction "36_36") (pintype "passive"))
      (node (ref "SV302") (pin "36") (pinfunction "36_36") (pintype "passive"))
      (node (ref "SV303") (pin "36") (pinfunction "36_36") (pintype "passive"))
      (node (ref "SV304") (pin "36") (pinfunction "36_36") (pintype "passive"))
    )
    (net (code "73") (name "SLOT_D6") (class "Default")
      (node (ref "IC101") (pin "12") (pinfunction "B7_12") (pintype "bidirectional"))
      (node (ref "SV301") (pin "34") (pinfunction "34_34") (pintype "passive"))
      (node (ref "SV302") (pin "34") (pinfunction "34_34") (pintype "passive"))
      (node (ref "SV303") (pin "34") (pinfunction "34_34") (pintype "passive"))
      (node (ref "SV304") (pin "34") (pinfunction "34_34") (pintype "passive"))
    )
    (net (code "74") (name "SLOT_D7") (class "Default")
      (node (ref "IC101") (pin "11") (pinfunction "B8_11") (pintype "bidirectional"))
      (node (ref "SV301") (pin "33") (pinfunction "33_33") (pintype "passive"))
      (node (ref "SV302") (pin "33") (pinfunction "33_33") (pintype "passive"))
      (node (ref "SV303") (pin "33") (pinfunction "33_33") (pintype "passive"))
      (node (ref "SV304") (pin "33") (pinfunction "33_33") (pintype "passive"))
    )
    (net (code "75") (name "SLOT_R{slash}~{W}") (class "Default")
      (node (ref "IC104") (pin "15") (pinfunction "B4_15") (pintype "bidirectional"))
      (node (ref "IC201") (pin "6") (pinfunction "IN6_6") (pintype "input"))
      (node (ref "SV301") (pin "23") (pinfunction "23_23") (pintype "passive"))
      (node (ref "SV302") (pin "23") (pinfunction "23_23") (pintype "passive"))
      (node (ref "SV303") (pin "23") (pinfunction "23_23") (pintype "passive"))
      (node (ref "SV304") (pin "23") (pinfunction "23_23") (pintype "passive"))
    )
    (net (code "76") (name "unconnected-(IC201-IN10-Pad10)") (class "Default")
      (node (ref "IC201") (pin "10") (pinfunction "IN10_10") (pintype "input"))
    )
    (net (code "77") (name "unconnected-(IC201-IN11-Pad11)") (class "Default")
      (node (ref "IC201") (pin "11") (pinfunction "IN11_11") (pintype "input"))
    )
    (net (code "78") (name "unconnected-(IC201-IO18-Pad18)") (class "Default")
      (node (ref "IC201") (pin "18") (pinfunction "IO18_18") (pintype "bidirectional"))
    )
    (net (code "79") (name "unconnected-(IC201-IO19-Pad19)") (class "Default")
      (node (ref "IC201") (pin "19") (pinfunction "IO19_19") (pintype "bidirectional"))
    )
    (net (code "80") (name "unconnected-(SV301-Pad29)") (class "Default")
      (node (ref "SV301") (pin "29") (pinfunction "29_29") (pintype "passive"))
    )
    (net (code "81") (name "unconnected-(SV302-Pad29)") (class "Default")
      (node (ref "SV302") (pin "29") (pinfunction "29_29") (pintype "passive"))
    )
    (net (code "82") (name "unconnected-(SV303-Pad29)") (class "Default")
      (node (ref "SV303") (pin "29") (pinfunction "29_29") (pintype "passive"))
    )
    (net (code "83") (name "unconnected-(SV304-Pad29)") (class "Default")
      (node (ref "SV304") (pin "29") (pinfunction "29_29") (pintype "passive"))
    )
    (net (code "84") (name "~{AS}") (class "Default")
      (node (ref "IC104") (pin "2") (pinfunction "A1_2") (pintype "bidirectional"))
      (node (ref "SV102") (pin "33") (pinfunction "33_33") (pintype "passive"))
      (node (ref "SV104") (pin "33") (pinfunction "33_33") (pintype "passive"))
    )
    (net (code "85") (name "~{BERR}") (class "Default")
      (node (ref "SV102") (pin "9") (pinfunction "9_9") (pintype "passive"))
      (node (ref "SV104") (pin "9") (pinfunction "9_9") (pintype "passive"))
    )
    (net (code "86") (name "~{BG}") (class "Default")
      (node (ref "SV102") (pin "25") (pinfunction "25_25") (pintype "passive"))
      (node (ref "SV104") (pin "25") (pinfunction "25_25") (pintype "passive"))
    )
    (net (code "87") (name "~{BR}") (class "Default")
      (node (ref "SV102") (pin "23") (pinfunction "23_23") (pintype "passive"))
      (node (ref "SV104") (pin "23") (pinfunction "23_23") (pintype "passive"))
    )
    (net (code "88") (name "~{BUF_ADDR_OE}") (class "Default")
      (node (ref "IC102") (pin "19") (pinfunction "G_19") (pintype "input"))
      (node (ref "IC103") (pin "19") (pinfunction "G_19") (pintype "input"))
      (node (ref "IC201") (pin "17") (pinfunction "IO17_17") (pintype "bidirectional"))
    )
    (net (code "89") (name "~{BUF_DATA_OE}") (class "Default")
      (node (ref "IC101") (pin "19") (pinfunction "G_19") (pintype "input"))
      (node (ref "IC201") (pin "16") (pinfunction "IO16_16") (pintype "bidirectional"))
    )
    (net (code "90") (name "~{BUS_CS}") (class "Default")
      (node (ref "IC201") (pin "2") (pinfunction "IN2_2") (pintype "input"))
      (node (ref "SV101") (pin "7") (pinfunction "7_7") (pintype "passive"))
      (node (ref "SV103") (pin "7") (pinfunction "7_7") (pintype "passive"))
    )
    (net (code "91") (name "~{BUS_DTACK}") (class "Default")
      (node (ref "IC201") (pin "14") (pinfunction "IO14_14") (pintype "bidirectional"))
      (node (ref "SV101") (pin "6") (pinfunction "6_6") (pintype "passive"))
      (node (ref "SV103") (pin "6") (pinfunction "6_6") (pintype "passive"))
    )
    (net (code "92") (name "~{BUS_IRQ}") (class "Default")
      (node (ref "R101") (pin "1") (pinfunction "1_1") (pintype "passive"))
      (node (ref "SV101") (pin "5") (pinfunction "5_5") (pintype "passive"))
      (node (ref "SV103") (pin "5") (pinfunction "5_5") (pintype "passive"))
      (node (ref "SV301") (pin "6") (pinfunction "6_6") (pintype "passive"))
      (node (ref "SV302") (pin "6") (pinfunction "6_6") (pintype "passive"))
      (node (ref "SV303") (pin "6") (pinfunction "6_6") (pintype "passive"))
      (node (ref "SV304") (pin "6") (pinfunction "6_6") (pintype "passive"))
    )
    (net (code "93") (name "~{DS}") (class "Default")
      (node (ref "IC104") (pin "3") (pinfunction "A2_3") (pintype "bidirectional"))
      (node (ref "SV102") (pin "31") (pinfunction "31_31") (pintype "passive"))
      (node (ref "SV104") (pin "31") (pinfunction "31_31") (pintype "passive"))
    )
    (net (code "94") (name "~{DTACK}") (class "Default")
      (node (ref "SV102") (pin "27") (pinfunction "27_27") (pintype "passive"))
      (node (ref "SV104") (pin "27") (pinfunction "27_27") (pintype "passive"))
    )
    (net (code "95") (name "~{HALT}") (class "Default")
      (node (ref "SV102") (pin "17") (pinfunction "17_17") (pintype "passive"))
      (node (ref "SV104") (pin "17") (pinfunction "17_17") (pintype "passive"))
    )
    (net (code "96") (name "~{RESET}") (class "Default")
      (node (ref "IC104") (pin "9") (pinfunction "A8_9") (pintype "bidirectional"))
      (node (ref "SV102") (pin "15") (pinfunction "15_15") (pintype "passive"))
      (node (ref "SV104") (pin "15") (pinfunction "15_15") (pintype "passive"))
    )
    (net (code "97") (name "~{SLOT_ACK}") (class "Default")
      (node (ref "IC201") (pin "13") (pinfunction "IN13_13") (pintype "input"))
      (node (ref "R102") (pin "1") (pinfunction "1_1") (pintype "passive"))
      (node (ref "SV301") (pin "24") (pinfunction "24_24") (pintype "passive"))
      (node (ref "SV302") (pin "24") (pinfunction "24_24") (pintype "passive"))
      (node (ref "SV303") (pin "24") (pinfunction "24_24") (pintype "passive"))
      (node (ref "SV304") (pin "24") (pinfunction "24_24") (pintype "passive"))
    )
    (net (code "98") (name "~{SLOT_AS}") (class "Default")
      (node (ref "IC104") (pin "18") (pinfunction "B1_18") (pintype "bidirectional"))
      (node (ref "SV301") (pin "32") (pinfunction "32_32") (pintype "passive"))
      (node (ref "SV302") (pin "32") (pinfunction "32_32") (pintype "passive"))
      (node (ref "SV303") (pin "32") (pinfunction "32_32") (pintype "passive"))
      (node (ref "SV304") (pin "32") (pinfunction "32_32") (pintype "passive"))
    )
    (net (code "99") (name "~{SLOT_CS0}") (class "Default")
      (node (ref "IC201") (pin "23") (pinfunction "IO23_23") (pintype "bidirectional"))
      (node (ref "LED301") (pin "C") (pinfunction "C_C") (pintype "passive"))
      (node (ref "SV301") (pin "5") (pinfunction "5_5") (pintype "passive"))
    )
    (net (code "100") (name "~{SLOT_CS1}") (class "Default")
      (node (ref "IC201") (pin "22") (pinfunction "IO22_22") (pintype "bidirectional"))
      (node (ref "LED302") (pin "C") (pinfunction "C_C") (pintype "passive"))
      (node (ref "SV303") (pin "5") (pinfunction "5_5") (pintype "passive"))
    )
    (net (code "101") (name "~{SLOT_CS2}") (class "Default")
      (node (ref "IC201") (pin "21") (pinfunction "IO21_21") (pintype "bidirectional"))
      (node (ref "LED303") (pin "C") (pinfunction "C_C") (pintype "passive"))
      (node (ref "SV302") (pin "5") (pinfunction "5_5") (pintype "passive"))
    )
    (net (code "102") (name "~{SLOT_CS3}") (class "Default")
      (node (ref "IC201") (pin "20") (pinfunction "IO20_20") (pintype "bidirectional"))
      (node (ref "LED304") (pin "C") (pinfunction "C_C") (pintype "passive"))
      (node (ref "SV304") (pin "5") (pinfunction "5_5") (pintype "passive"))
    )
    (net (code "103") (name "~{SLOT_DS}") (class "Default")
      (node (ref "IC104") (pin "17") (pinfunction "B2_17") (pintype "bidirectional"))
      (node (ref "IC201") (pin "9") (pinfunction "IN9_9") (pintype "input"))
      (node (ref "SV301") (pin "31") (pinfunction "31_31") (pintype "passive"))
      (node (ref "SV302") (pin "31") (pinfunction "31_31") (pintype "passive"))
      (node (ref "SV303") (pin "31") (pinfunction "31_31") (pintype "passive"))
      (node (ref "SV304") (pin "31") (pinfunction "31_31") (pintype "passive"))
    )
    (net (code "104") (name "~{SLOT_RESET}") (class "Default")
      (node (ref "IC104") (pin "11") (pinfunction "B8_11") (pintype "bidirectional"))
      (node (ref "IC201") (pin "8") (pinfunction "IN8_8") (pintype "input"))
      (node (ref "SV301") (pin "30") (pinfunction "30_30") (pintype "passive"))
      (node (ref "SV302") (pin "30") (pinfunction "30_30") (pintype "passive"))
      (node (ref "SV303") (pin "30") (pinfunction "30_30") (pintype "passive"))
      (node (ref "SV304") (pin "30") (pinfunction "30_30") (pintype "passive"))
    )
    (net (code "105") (name "~{VPA}") (class "Default")
      (node (ref "SV102") (pin "11") (pinfunction "11_11") (pintype "passive"))
      (node (ref "SV104") (pin "11") (pinfunction "11_11") (pintype "passive"))
    )
  )
)
